# PCB_SCHEMATIC.net
KiCad netlist of a schematic drawn in EasyEDA
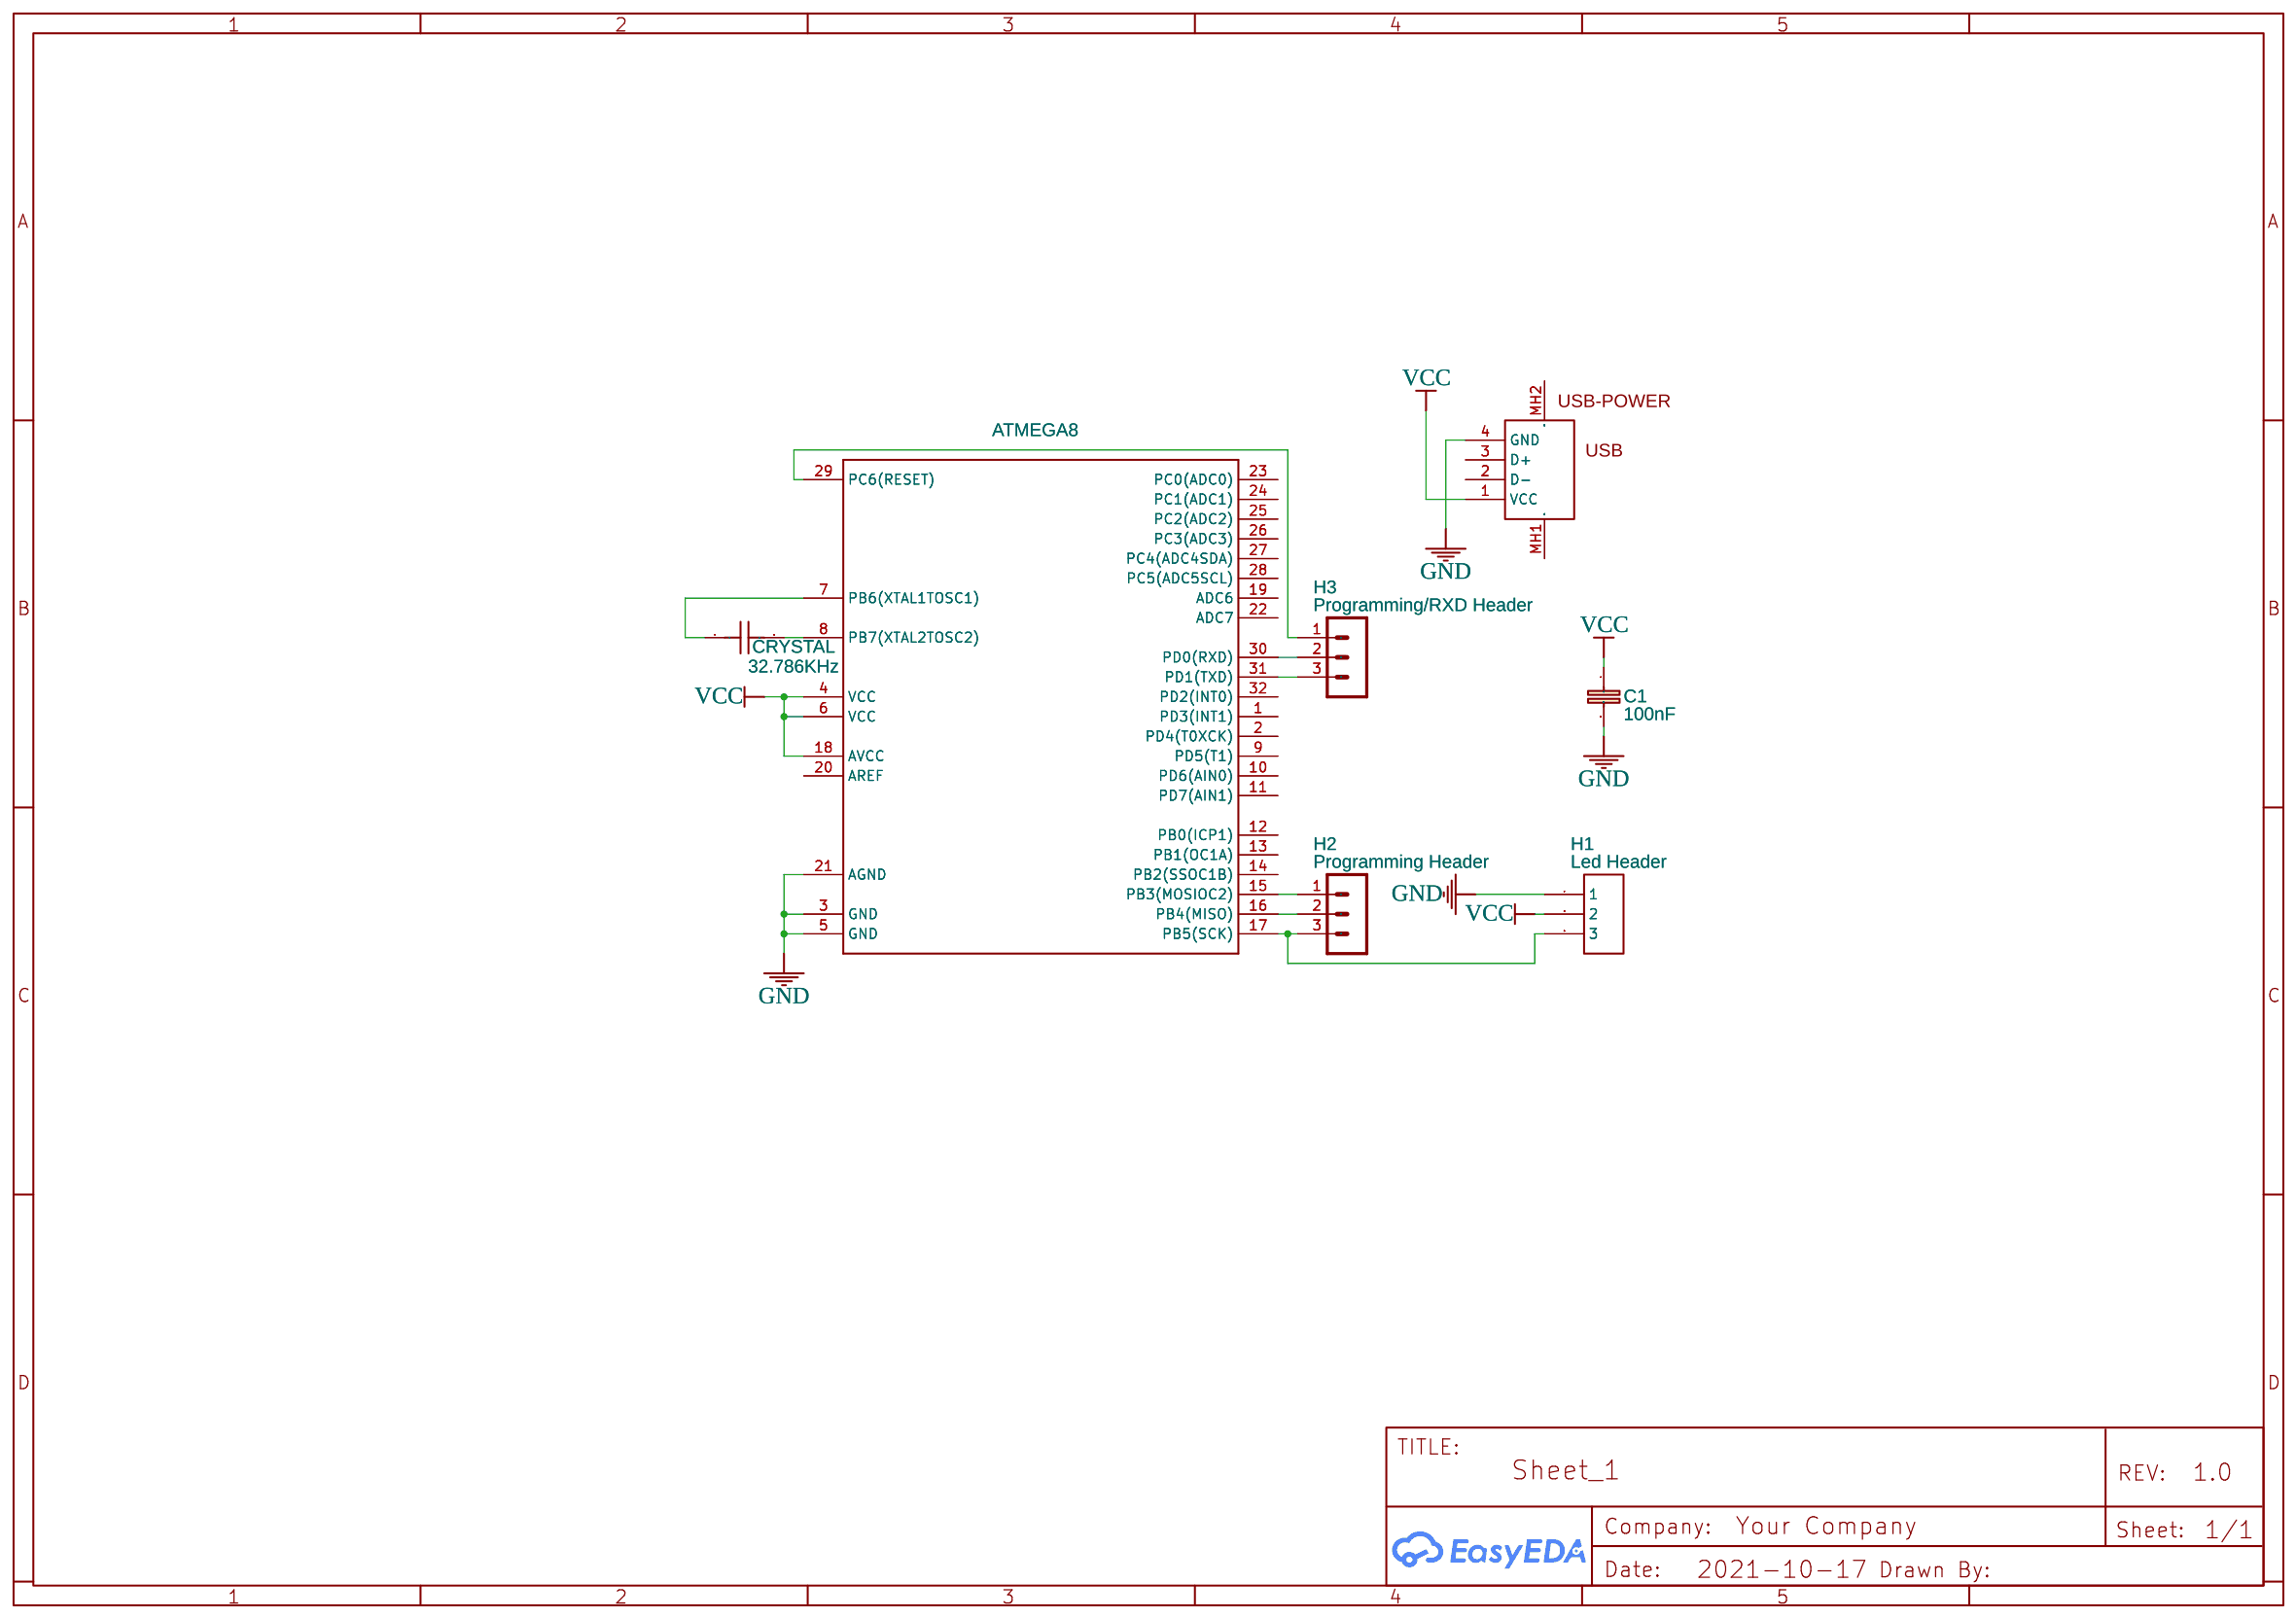
[diagram p0: schematic sheet]

(export (version "E")
  (design (tool "Eeschema 10.0.6"))
  (components
    (comp (ref "C1") (value "100nF") (libsource (lib "") (part "CAPACITOR_NPOL-1206")))
    (comp (ref "CRYSTAL") (value "32.786KHz") (libsource (lib "") (part "C_0805_US")))
    (comp (ref "H1")
      (value "Led Header")
      (fields
        (field (name "BOM_Manufacturer Part") "Female header pitch2.54mm")
        (field (name "BOM_Supplier Part") "SSM-104-T-SV-BE-ND")
      )
      (libsource (lib "") (part "Header_Female_2.54mm_1x3_SMD"))
    )
    (comp (ref "H2") (value "Programming Header") (libsource (lib "") (part "3PIN-HEADER")))
    (comp (ref "H3") (value "Programming/RXD Header") (libsource (lib "") (part "3PIN-HEADER")))
    (comp (ref "U1") (value "ATMEGA8") (libsource (lib "") (part "ATMEGA8-AU")))
    (comp (ref "U4") (value "USB") (libsource (lib "") (part "USB_MALE_USBKey")))
  )
  (nets
    (net (code "1") (name "GND") (class "Default")
      (node (ref "C1") (pin "2") (pinfunction "2_2") (pintype "unspecified"))
      (node (ref "H1") (pin "1") (pinfunction "1_1") (pintype "input"))
      (node (ref "U1") (pin "21") (pinfunction "AGND_21") (pintype "passive"))
      (node (ref "U1") (pin "3") (pinfunction "GND_3") (pintype "passive"))
      (node (ref "U1") (pin "5") (pinfunction "GND_5") (pintype "passive"))
      (node (ref "U4") (pin "4") (pinfunction "GND_4") (pintype "input"))
    )
    (net (code "2") (name "Net-(U1-PB3(MOSIOC2))") (class "Default")
      (node (ref "H2") (pin "1") (pinfunction "1_1") (pintype "bidirectional"))
      (node (ref "U1") (pin "15") (pinfunction "PB3(MOSIOC2)_15") (pintype "unspecified"))
    )
    (net (code "3") (name "Net-(U1-PB4(MISO))") (class "Default")
      (node (ref "H2") (pin "2") (pinfunction "2_2") (pintype "bidirectional"))
      (node (ref "U1") (pin "16") (pinfunction "PB4(MISO)_16") (pintype "unspecified"))
    )
    (net (code "4") (name "Net-(U1-PB5(SCK))") (class "Default")
      (node (ref "H1") (pin "3") (pinfunction "3_3") (pintype "input"))
      (node (ref "H2") (pin "3") (pinfunction "3_3") (pintype "bidirectional"))
      (node (ref "U1") (pin "17") (pinfunction "PB5(SCK)_17") (pintype "unspecified"))
    )
    (net (code "5") (name "Net-(U1-PB6(XTAL1TOSC1))") (class "Default")
      (node (ref "CRYSTAL") (pin "1") (pinfunction "1_1") (pintype "unspecified"))
      (node (ref "U1") (pin "7") (pinfunction "PB6(XTAL1TOSC1)_7") (pintype "unspecified"))
    )
    (net (code "6") (name "Net-(U1-PB7(XTAL2TOSC2))") (class "Default")
      (node (ref "CRYSTAL") (pin "2") (pinfunction "2_2") (pintype "unspecified"))
      (node (ref "U1") (pin "8") (pinfunction "PB7(XTAL2TOSC2)_8") (pintype "unspecified"))
    )
    (net (code "7") (name "Net-(U1-PC6(RESET))") (class "Default")
      (node (ref "H3") (pin "1") (pinfunction "1_1") (pintype "bidirectional"))
      (node (ref "U1") (pin "29") (pinfunction "PC6(RESET)_29") (pintype "unspecified"))
    )
    (net (code "8") (name "Net-(U1-PD0(RXD))") (class "Default")
      (node (ref "H3") (pin "2") (pinfunction "2_2") (pintype "bidirectional"))
      (node (ref "U1") (pin "30") (pinfunction "PD0(RXD)_30") (pintype "unspecified"))
    )
    (net (code "9") (name "Net-(U1-PD1(TXD))") (class "Default")
      (node (ref "H3") (pin "3") (pinfunction "3_3") (pintype "bidirectional"))
      (node (ref "U1") (pin "31") (pinfunction "PD1(TXD)_31") (pintype "unspecified"))
    )
    (net (code "10") (name "VCC") (class "Default")
      (node (ref "C1") (pin "1") (pinfunction "1_1") (pintype "unspecified"))
      (node (ref "H1") (pin "2") (pinfunction "2_2") (pintype "input"))
      (node (ref "U1") (pin "18") (pinfunction "AVCC_18") (pintype "unspecified"))
      (node (ref "U1") (pin "4") (pinfunction "VCC_4") (pintype "passive"))
      (node (ref "U1") (pin "6") (pinfunction "VCC_6") (pintype "passive"))
      (node (ref "U4") (pin "1") (pinfunction "VCC_1") (pintype "input"))
    )
    (net (code "11") (name "unconnected-(U1-ADC6-Pad19)") (class "Default")
      (node (ref "U1") (pin "19") (pinfunction "ADC6_19") (pintype "unspecified"))
    )
    (net (code "12") (name "unconnected-(U1-ADC7-Pad22)") (class "Default")
      (node (ref "U1") (pin "22") (pinfunction "ADC7_22") (pintype "unspecified"))
    )
    (net (code "13") (name "unconnected-(U1-AREF-Pad20)") (class "Default")
      (node (ref "U1") (pin "20") (pinfunction "AREF_20") (pintype "unspecified"))
    )
    (net (code "14") (name "unconnected-(U1-PB0(ICP1)-Pad12)") (class "Default")
      (node (ref "U1") (pin "12") (pinfunction "PB0(ICP1)_12") (pintype "unspecified"))
    )
    (net (code "15") (name "unconnected-(U1-PB1(OC1A)-Pad13)") (class "Default")
      (node (ref "U1") (pin "13") (pinfunction "PB1(OC1A)_13") (pintype "unspecified"))
    )
    (net (code "16") (name "unconnected-(U1-PB2(SSOC1B)-Pad14)") (class "Default")
      (node (ref "U1") (pin "14") (pinfunction "PB2(SSOC1B)_14") (pintype "unspecified"))
    )
    (net (code "17") (name "unconnected-(U1-PC0(ADC0)-Pad23)") (class "Default")
      (node (ref "U1") (pin "23") (pinfunction "PC0(ADC0)_23") (pintype "unspecified"))
    )
    (net (code "18") (name "unconnected-(U1-PC1(ADC1)-Pad24)") (class "Default")
      (node (ref "U1") (pin "24") (pinfunction "PC1(ADC1)_24") (pintype "unspecified"))
    )
    (net (code "19") (name "unconnected-(U1-PC2(ADC2)-Pad25)") (class "Default")
      (node (ref "U1") (pin "25") (pinfunction "PC2(ADC2)_25") (pintype "unspecified"))
    )
    (net (code "20") (name "unconnected-(U1-PC3(ADC3)-Pad26)") (class "Default")
      (node (ref "U1") (pin "26") (pinfunction "PC3(ADC3)_26") (pintype "unspecified"))
    )
    (net (code "21") (name "unconnected-(U1-PC4(ADC4SDA)-Pad27)") (class "Default")
      (node (ref "U1") (pin "27") (pinfunction "PC4(ADC4SDA)_27") (pintype "unspecified"))
    )
    (net (code "22") (name "unconnected-(U1-PC5(ADC5SCL)-Pad28)") (class "Default")
      (node (ref "U1") (pin "28") (pinfunction "PC5(ADC5SCL)_28") (pintype "unspecified"))
    )
    (net (code "23") (name "unconnected-(U1-PD2(INT0)-Pad32)") (class "Default")
      (node (ref "U1") (pin "32") (pinfunction "PD2(INT0)_32") (pintype "unspecified"))
    )
    (net (code "24") (name "unconnected-(U1-PD3(INT1)-Pad1)") (class "Default")
      (node (ref "U1") (pin "1") (pinfunction "PD3(INT1)_1") (pintype "unspecified"))
    )
    (net (code "25") (name "unconnected-(U1-PD4(T0XCK)-Pad2)") (class "Default")
      (node (ref "U1") (pin "2") (pinfunction "PD4(T0XCK)_2") (pintype "unspecified"))
    )
    (net (code "26") (name "unconnected-(U1-PD5(T1)-Pad9)") (class "Default")
      (node (ref "U1") (pin "9") (pinfunction "PD5(T1)_9") (pintype "unspecified"))
    )
    (net (code "27") (name "unconnected-(U1-PD6(AIN0)-Pad10)") (class "Default")
      (node (ref "U1") (pin "10") (pinfunction "PD6(AIN0)_10") (pintype "unspecified"))
    )
    (net (code "28") (name "unconnected-(U1-PD7(AIN1)-Pad11)") (class "Default")
      (node (ref "U1") (pin "11") (pinfunction "PD7(AIN1)_11") (pintype "unspecified"))
    )
    (net (code "29") (name "unconnected-(U4-D+-Pad3)") (class "Default")
      (node (ref "U4") (pin "3") (pinfunction "D+_3") (pintype "input"))
    )
    (net (code "30") (name "unconnected-(U4-D--Pad2)") (class "Default")
      (node (ref "U4") (pin "2") (pinfunction "D-_2") (pintype "input"))
    )
    (net (code "31") (name "unconnected-(U4-PadMH1)") (class "Default")
      (node (ref "U4") (pin "MH1") (pinfunction "MH1_MH1") (pintype "unspecified"))
    )
    (net (code "32") (name "unconnected-(U4-PadMH2)") (class "Default")
      (node (ref "U4") (pin "MH2") (pinfunction "MH2_MH2") (pintype "unspecified"))
    )
  )
)
